# 201106.net
KiCad netlist of a schematic drawn in Altium Designer
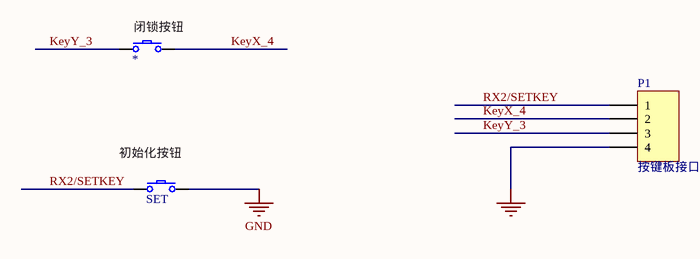
[diagram p0: 贴锁按键板201106.SchDoc]

(export (version "E")
  (design (tool "Eeschema 10.0.6"))
  (components
    (comp (ref "*")
      (value "SW")
      (footprint "SW3")
      (description "Switch")
      (libsource (lib "MyLibrary") (part "SW"))
    )
    (comp (ref "P1")
      (value "按键板接口")
      (footprint "4P-1.25_1")
      (description "Header, 4-Pin")
      (fields (field (name "PUBLISHER") "Altium Limited"))
      (libsource (lib "贴锁控制板") (part "Header 4_1"))
    )
    (comp (ref "SET")
      (value "SW")
      (footprint "SW3")
      (description "Switch")
      (libsource (lib "MyLibrary") (part "SW"))
    )
  )
  (nets
    (net (code "1") (name "/KeyX_4") (class "Default")
      (node (ref "*") (pin "2") (pintype "passive"))
      (node (ref "P1") (pin "2") (pinfunction "2_2") (pintype "passive"))
    )
    (net (code "2") (name "/KeyY_3") (class "Default")
      (node (ref "*") (pin "1") (pintype "passive"))
      (node (ref "P1") (pin "3") (pinfunction "3_3") (pintype "passive"))
    )
    (net (code "3") (name "/RX2{slash}SETKEY") (class "Default")
      (node (ref "P1") (pin "1") (pinfunction "1_1") (pintype "passive"))
      (node (ref "SET") (pin "1") (pintype "passive"))
    )
    (net (code "4") (name "GND") (class "Default")
      (node (ref "P1") (pin "4") (pinfunction "4_4") (pintype "passive"))
      (node (ref "SET") (pin "2") (pintype "passive"))
    )
  )
)
